# mosV2_0.net
KiCad netlist of a schematic drawn in Altium Designer
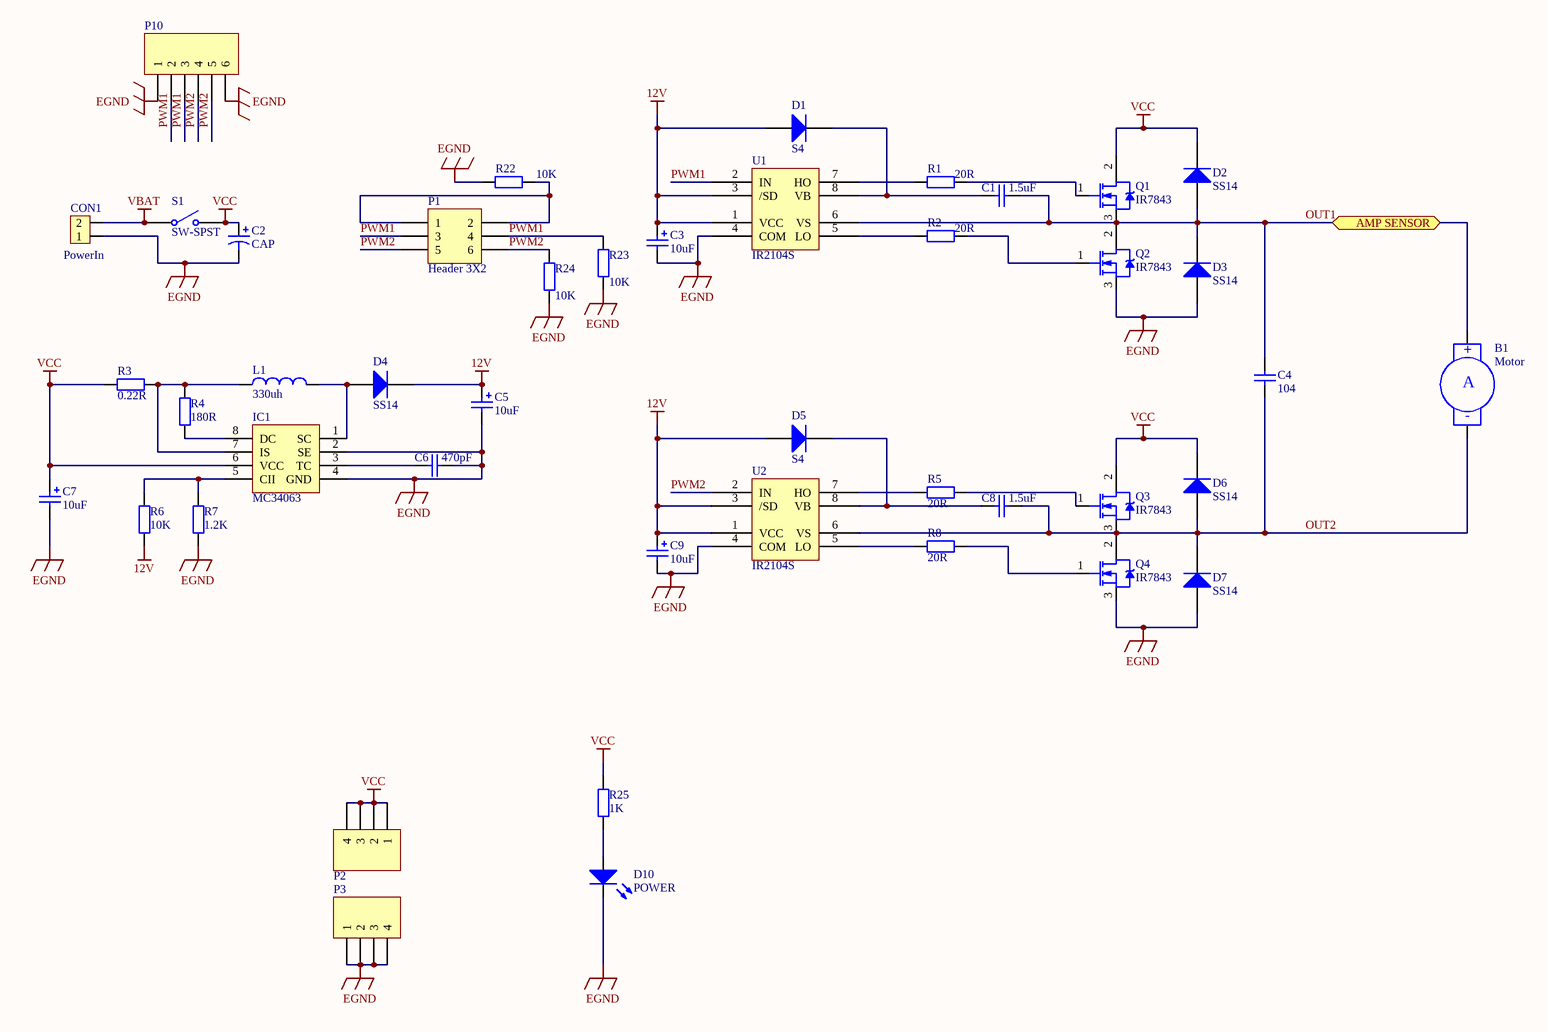
[diagram p0: 自控mosV2.0.SchDoc]

(export (version "E")
  (design (tool "Eeschema 10.0.6"))
  (components
    (comp (ref "B1")
      (value "Motor")
      (footprint "KF301-2P")
      (description "Servo Motor")
      (libsource (lib "landzo_mos") (part "Motor Servo"))
    )
    (comp (ref "C1")
      (value "1.5uF")
      (footprint "C2012")
      (description "Capacitor")
      (fields (field (name "Comment") "Cap") (field (name "PUBLISHER") "Altium Limited"))
      (libsource (lib "Miscellaneous Devices") (part "Cap"))
    )
    (comp (ref "C2") (value "CAP") (footprint "SMD-EC-F8") (libsource (lib "电赛") (part "CAP+")))
    (comp (ref "C3")
      (value "10uF")
      (footprint "C2012")
      (description "Polarized Capacitor (Radial)")
      (fields (field (name "Comment") "Cap Pol1") (field (name "PUBLISHER") "Altium Limited"))
      (libsource (lib "landzo_mos") (part "Cap Pol1"))
    )
    (comp (ref "C4")
      (value "104")
      (footprint "C2012")
      (description "Capacitor")
      (fields (field (name "Comment") "Cap") (field (name "PUBLISHER") "Altium Limited"))
      (libsource (lib "Miscellaneous Devices") (part "Cap"))
    )
    (comp (ref "C5")
      (value "10uF")
      (footprint "1206C")
      (description "Polarized Capacitor (Radial)")
      (fields (field (name "Comment") "Cap Pol1") (field (name "PUBLISHER") "Altium Limited"))
      (libsource (lib "landzo_mos") (part "Cap Pol1"))
    )
    (comp (ref "C6")
      (value "470pF")
      (footprint "C2012")
      (description "Capacitor")
      (fields (field (name "Comment") "Cap") (field (name "PUBLISHER") "Altium Limited"))
      (libsource (lib "Miscellaneous Devices") (part "Cap"))
    )
    (comp (ref "C7")
      (value "10uF")
      (footprint "1206C")
      (description "Polarized Capacitor (Radial)")
      (fields (field (name "Comment") "Cap Pol1") (field (name "PUBLISHER") "Altium Limited"))
      (libsource (lib "landzo_mos") (part "Cap Pol1"))
    )
    (comp (ref "C8")
      (value "1.5uF")
      (footprint "C2012")
      (description "Capacitor")
      (fields (field (name "Comment") "Cap") (field (name "PUBLISHER") "Altium Limited"))
      (libsource (lib "Miscellaneous Devices") (part "Cap"))
    )
    (comp (ref "C9")
      (value "10uF")
      (footprint "C2012")
      (description "Polarized Capacitor (Radial)")
      (fields (field (name "Comment") "Cap Pol1") (field (name "PUBLISHER") "Altium Limited"))
      (libsource (lib "landzo_mos") (part "Cap Pol1"))
    )
    (comp (ref "CON1")
      (value "PowerIn")
      (footprint "KF301-2P")
      (description "Header, 2-Pin")
      (libsource (lib "landzo_mos") (part "Header 2"))
    )
    (comp (ref "D1")
      (value "S4")
      (footprint "R2012")
      (description "1 Amp General Purpose Rectifier")
      (fields (field (name "PUBLISHER") "Altium Limited"))
      (libsource (lib "Miscellaneous Devices") (part "Diode 1N4007"))
    )
    (comp (ref "D2")
      (value "SS14")
      (footprint "hole-chip diode")
      (description "1 Amp General Purpose Rectifier")
      (fields (field (name "PUBLISHER") "Altium Limited"))
      (libsource (lib "Miscellaneous Devices") (part "Diode 1N4007"))
    )
    (comp (ref "D3")
      (value "SS14")
      (footprint "hole-chip diode")
      (description "1 Amp General Purpose Rectifier")
      (fields (field (name "PUBLISHER") "Altium Limited"))
      (libsource (lib "Miscellaneous Devices") (part "Diode 1N4007"))
    )
    (comp (ref "D4")
      (value "SS14")
      (footprint "hole-chip diode")
      (description "1 Amp General Purpose Rectifier")
      (fields (field (name "PUBLISHER") "Altium Limited"))
      (libsource (lib "Miscellaneous Devices") (part "Diode 1N4007"))
    )
    (comp (ref "D5")
      (value "S4")
      (footprint "R2012")
      (description "1 Amp General Purpose Rectifier")
      (fields (field (name "PUBLISHER") "Altium Limited"))
      (libsource (lib "Miscellaneous Devices") (part "Diode 1N4007"))
    )
    (comp (ref "D6")
      (value "SS14")
      (footprint "hole-chip diode")
      (description "1 Amp General Purpose Rectifier")
      (fields (field (name "PUBLISHER") "Altium Limited"))
      (libsource (lib "Miscellaneous Devices") (part "Diode 1N4007"))
    )
    (comp (ref "D7")
      (value "SS14")
      (footprint "hole-chip diode")
      (description "1 Amp General Purpose Rectifier")
      (fields (field (name "PUBLISHER") "Altium Limited"))
      (libsource (lib "Miscellaneous Devices") (part "Diode 1N4007"))
    )
    (comp (ref "D10")
      (value "POWER")
      (footprint "C2012")
      (description "Typical INFRARED GaAs LED")
      (libsource (lib "K60-V4.0") (part "LED"))
    )
    (comp (ref "IC1")
      (value "MC34063")
      (footprint "MOS motor driving module:MC34063")
      (libsource (lib "Landzo") (part "MC34063"))
    )
    (comp (ref "L1")
      (value "330uh")
      (footprint "SMD-EC-F10")
      (description "Inductor")
      (fields (field (name "PUBLISHER") "Altium Limited"))
      (libsource (lib "landzo_mos") (part "Inductor"))
    )
    (comp (ref "P1")
      (value "Header 3X2")
      (footprint "HDR2X3")
      (description "Header, 3-Pin, Dual row")
      (fields (field (name "PUBLISHER") "Altium Limited"))
      (libsource (lib "Miscellaneous Connectors") (part "Header 3X2"))
    )
    (comp (ref "P2")
      (value "Header 4")
      (footprint "HDR1X4")
      (description "Header, 4-Pin")
      (fields (field (name "PUBLISHER") "Altium Limited"))
      (libsource (lib "Sparks") (part "Header 4"))
    )
    (comp (ref "P3")
      (value "Header 4")
      (footprint "HDR1X4")
      (description "Header, 4-Pin")
      (fields (field (name "PUBLISHER") "Altium Limited"))
      (libsource (lib "") (part "Header 4_1"))
    )
    (comp (ref "P10")
      (value "Header 6")
      (footprint "FFC/SM1.0-2H6")
      (description "Header, 6-Pin")
      (fields (field (name "PUBLISHER") "Altium Limited"))
      (libsource (lib "Miscellaneous Connectors") (part "Header 6"))
    )
    (comp (ref "Q1")
      (value "IR7843")
      (footprint "LR7843")
      (description "N-Channel Power MOSFET")
      (fields (field (name "PUBLISHER") "Altium Limited"))
      (libsource (lib "MOS motor driving module ") (part "NMOS-2"))
    )
    (comp (ref "Q2")
      (value "IR7843")
      (footprint "LR7843")
      (description "N-Channel Power MOSFET")
      (fields (field (name "PUBLISHER") "Altium Limited"))
      (libsource (lib "MOS motor driving module ") (part "NMOS-2"))
    )
    (comp (ref "Q3")
      (value "IR7843")
      (footprint "LR7843")
      (description "N-Channel Power MOSFET")
      (fields (field (name "PUBLISHER") "Altium Limited"))
      (libsource (lib "MOS motor driving module ") (part "NMOS-2"))
    )
    (comp (ref "Q4")
      (value "IR7843")
      (footprint "LR7843")
      (description "N-Channel Power MOSFET")
      (fields (field (name "PUBLISHER") "Altium Limited"))
      (libsource (lib "MOS motor driving module ") (part "NMOS-2"))
    )
    (comp (ref "R1")
      (value "20R")
      (footprint "R2012")
      (description "Resistor")
      (fields (field (name "Comment") "Res2") (field (name "PUBLISHER") "Altium Limited"))
      (libsource (lib "landzo_mos") (part "Res2"))
    )
    (comp (ref "R2")
      (value "20R")
      (footprint "R2012")
      (description "Resistor")
      (fields (field (name "Comment") "Res2") (field (name "PUBLISHER") "Altium Limited"))
      (libsource (lib "landzo_mos") (part "Res2"))
    )
    (comp (ref "R3")
      (value "0.22R")
      (footprint "SK54")
      (description "Resistor")
      (fields (field (name "Comment") "Res2") (field (name "PUBLISHER") "Altium Limited"))
      (libsource (lib "landzo_mos") (part "Res2"))
    )
    (comp (ref "R4")
      (value "180R")
      (footprint "R2012")
      (description "Resistor")
      (fields (field (name "Comment") "Res2") (field (name "PUBLISHER") "Altium Limited"))
      (libsource (lib "") (part "Res2_1"))
    )
    (comp (ref "R5")
      (value "20R")
      (footprint "R2012")
      (description "Resistor")
      (fields (field (name "Comment") "Res2") (field (name "PUBLISHER") "Altium Limited"))
      (libsource (lib "landzo_mos") (part "Res2"))
    )
    (comp (ref "R6")
      (value "10K")
      (footprint "R2012")
      (description "Resistor")
      (fields (field (name "Comment") "Res2") (field (name "PUBLISHER") "Altium Limited"))
      (libsource (lib "") (part "Res2_1"))
    )
    (comp (ref "R7")
      (value "1.2K")
      (footprint "R2012")
      (description "Resistor")
      (fields (field (name "Comment") "Res2") (field (name "PUBLISHER") "Altium Limited"))
      (libsource (lib "") (part "Res2_1"))
    )
    (comp (ref "R8")
      (value "20R")
      (footprint "R2012")
      (description "Resistor")
      (fields (field (name "Comment") "Res2") (field (name "PUBLISHER") "Altium Limited"))
      (libsource (lib "landzo_mos") (part "Res2"))
    )
    (comp (ref "R22")
      (value "10K")
      (footprint "1206(2)")
      (description "Resistor")
      (fields (field (name "Comment") "Res2") (field (name "PUBLISHER") "Altium Limited"))
      (libsource (lib "Miscellaneous Devices") (part "Res2"))
    )
    (comp (ref "R23")
      (value "10K")
      (footprint "R2012")
      (description "Resistor")
      (fields (field (name "Comment") "Res2") (field (name "PUBLISHER") "Altium Limited"))
      (libsource (lib "") (part "Res2_1"))
    )
    (comp (ref "R24")
      (value "10K")
      (footprint "R2012")
      (description "Resistor")
      (fields (field (name "Comment") "Res2") (field (name "PUBLISHER") "Altium Limited"))
      (libsource (lib "") (part "Res2_1"))
    )
    (comp (ref "R25")
      (value "1K")
      (footprint "R2012")
      (description "Resistor of led")
      (libsource (lib "K60-V4.0") (part "Res"))
    )
    (comp (ref "S1")
      (value "SW-SPST")
      (footprint "SW-125V6A(-)")
      (description "Single-Pole, Single-Throw Switch")
      (fields (field (name "PUBLISHER") "Altium Limited"))
      (libsource (lib "Miscellaneous Devices") (part "SW-SPST"))
    )
    (comp (ref "U1")
      (value "IR2104S")
      (footprint "IR2104")
      (libsource (lib "MOS motor driving module ") (part "Component_1_1"))
    )
    (comp (ref "U2")
      (value "IR2104S")
      (footprint "IR2104")
      (libsource (lib "MOS motor driving module ") (part "Component_1_1"))
    )
  )
  (nets
    (net (code "1") (name "/OUT1") (class "Default")
      (node (ref "B1") (pin "1") (pinfunction "+_1") (pintype "passive"))
      (node (ref "C1") (pin "1") (pinfunction "1_1") (pintype "passive"))
      (node (ref "C4") (pin "1") (pinfunction "1_1") (pintype "passive"))
      (node (ref "D2") (pin "1") (pinfunction "A_1") (pintype "passive"))
      (node (ref "D3") (pin "2") (pinfunction "K_2") (pintype "passive"))
      (node (ref "Q1") (pin "3") (pinfunction "S_3") (pintype "passive"))
      (node (ref "Q2") (pin "2") (pinfunction "D_2") (pintype "passive"))
      (node (ref "U1") (pin "6") (pinfunction "VS_6") (pintype "passive"))
    )
    (net (code "2") (name "/OUT2") (class "Default")
      (node (ref "B1") (pin "2") (pinfunction "-_2") (pintype "passive"))
      (node (ref "C4") (pin "2") (pinfunction "2_2") (pintype "passive"))
      (node (ref "C8") (pin "1") (pinfunction "1_1") (pintype "passive"))
      (node (ref "D6") (pin "1") (pinfunction "A_1") (pintype "passive"))
      (node (ref "D7") (pin "2") (pinfunction "K_2") (pintype "passive"))
      (node (ref "Q3") (pin "3") (pinfunction "S_3") (pintype "passive"))
      (node (ref "Q4") (pin "2") (pinfunction "D_2") (pintype "passive"))
      (node (ref "U2") (pin "6") (pinfunction "VS_6") (pintype "passive"))
    )
    (net (code "3") (name "/PWM1") (class "Default")
      (node (ref "P1") (pin "3") (pinfunction "3_3") (pintype "passive"))
      (node (ref "P1") (pin "4") (pinfunction "4_4") (pintype "passive"))
      (node (ref "P10") (pin "2") (pinfunction "2_2") (pintype "passive"))
      (node (ref "P10") (pin "3") (pinfunction "3_3") (pintype "passive"))
      (node (ref "R23") (pin "2") (pinfunction "2_2") (pintype "passive"))
      (node (ref "U1") (pin "2") (pinfunction "IN_2") (pintype "passive"))
    )
    (net (code "4") (name "/PWM2") (class "Default")
      (node (ref "P1") (pin "5") (pinfunction "5_5") (pintype "passive"))
      (node (ref "P1") (pin "6") (pinfunction "6_6") (pintype "passive"))
      (node (ref "P10") (pin "4") (pinfunction "4_4") (pintype "passive"))
      (node (ref "P10") (pin "5") (pinfunction "5_5") (pintype "passive"))
      (node (ref "R24") (pin "2") (pinfunction "2_2") (pintype "passive"))
      (node (ref "U2") (pin "2") (pinfunction "IN_2") (pintype "passive"))
    )
    (net (code "5") (name "12V") (class "Default")
      (node (ref "C3") (pin "1") (pinfunction "1_1") (pintype "passive"))
      (node (ref "C5") (pin "1") (pinfunction "1_1") (pintype "passive"))
      (node (ref "C9") (pin "1") (pinfunction "1_1") (pintype "passive"))
      (node (ref "D1") (pin "1") (pinfunction "A_1") (pintype "passive"))
      (node (ref "D4") (pin "2") (pinfunction "K_2") (pintype "passive"))
      (node (ref "D5") (pin "1") (pinfunction "A_1") (pintype "passive"))
      (node (ref "R6") (pin "1") (pinfunction "1_1") (pintype "passive"))
      (node (ref "U1") (pin "1") (pinfunction "VCC_1") (pintype "passive"))
      (node (ref "U1") (pin "3") (pinfunction "/SD_3") (pintype "passive"))
      (node (ref "U2") (pin "1") (pinfunction "VCC_1") (pintype "passive"))
      (node (ref "U2") (pin "3") (pinfunction "/SD_3") (pintype "passive"))
    )
    (net (code "6") (name "EGND") (class "Default")
      (node (ref "C2") (pin "2") (pinfunction "2_2") (pintype "passive"))
      (node (ref "C3") (pin "2") (pinfunction "2_2") (pintype "passive"))
      (node (ref "C5") (pin "2") (pinfunction "2_2") (pintype "passive"))
      (node (ref "C6") (pin "1") (pinfunction "1_1") (pintype "passive"))
      (node (ref "C7") (pin "2") (pinfunction "2_2") (pintype "passive"))
      (node (ref "C9") (pin "2") (pinfunction "2_2") (pintype "passive"))
      (node (ref "CON1") (pin "1") (pinfunction "1_1") (pintype "passive"))
      (node (ref "D10") (pin "2") (pinfunction "2_2") (pintype "passive"))
      (node (ref "D3") (pin "1") (pinfunction "A_1") (pintype "passive"))
      (node (ref "D7") (pin "1") (pinfunction "A_1") (pintype "passive"))
      (node (ref "IC1") (pin "2") (pinfunction "SE_2") (pintype "passive"))
      (node (ref "IC1") (pin "4") (pinfunction "GND_4") (pintype "passive"))
      (node (ref "P10") (pin "1") (pinfunction "1_1") (pintype "passive"))
      (node (ref "P10") (pin "6") (pinfunction "6_6") (pintype "passive"))
      (node (ref "P3") (pin "1") (pinfunction "1_1") (pintype "passive"))
      (node (ref "P3") (pin "2") (pinfunction "2_2") (pintype "passive"))
      (node (ref "P3") (pin "3") (pinfunction "3_3") (pintype "passive"))
      (node (ref "P3") (pin "4") (pinfunction "4_4") (pintype "passive"))
      (node (ref "Q2") (pin "3") (pinfunction "S_3") (pintype "passive"))
      (node (ref "Q4") (pin "3") (pinfunction "S_3") (pintype "passive"))
      (node (ref "R22") (pin "1") (pinfunction "1_1") (pintype "passive"))
      (node (ref "R23") (pin "1") (pinfunction "1_1") (pintype "passive"))
      (node (ref "R24") (pin "1") (pinfunction "1_1") (pintype "passive"))
      (node (ref "R7") (pin "1") (pinfunction "1_1") (pintype "passive"))
      (node (ref "U1") (pin "4") (pinfunction "COM_4") (pintype "passive"))
      (node (ref "U2") (pin "4") (pinfunction "COM_4") (pintype "passive"))
    )
    (net (code "7") (name "Net-(D1-K)") (class "Default")
      (node (ref "C1") (pin "2") (pinfunction "2_2") (pintype "passive"))
      (node (ref "D1") (pin "2") (pinfunction "K_2") (pintype "passive"))
      (node (ref "U1") (pin "8") (pinfunction "VB_8") (pintype "passive"))
    )
    (net (code "8") (name "Net-(D4-A)") (class "Default")
      (node (ref "D4") (pin "1") (pinfunction "A_1") (pintype "passive"))
      (node (ref "IC1") (pin "1") (pinfunction "SC_1") (pintype "passive"))
      (node (ref "L1") (pin "2") (pinfunction "2_2") (pintype "passive"))
    )
    (net (code "9") (name "Net-(D5-K)") (class "Default")
      (node (ref "C8") (pin "2") (pinfunction "2_2") (pintype "passive"))
      (node (ref "D5") (pin "2") (pinfunction "K_2") (pintype "passive"))
      (node (ref "U2") (pin "8") (pinfunction "VB_8") (pintype "passive"))
    )
    (net (code "10") (name "Net-(D10-Pad1)") (class "Default")
      (node (ref "D10") (pin "1") (pinfunction "1_1") (pintype "passive"))
      (node (ref "R25") (pin "1") (pinfunction "1_1") (pintype "passive"))
    )
    (net (code "11") (name "Net-(IC1-CII)") (class "Default")
      (node (ref "IC1") (pin "5") (pinfunction "CII_5") (pintype "passive"))
      (node (ref "R6") (pin "2") (pinfunction "2_2") (pintype "passive"))
      (node (ref "R7") (pin "2") (pinfunction "2_2") (pintype "passive"))
    )
    (net (code "12") (name "Net-(IC1-DC)") (class "Default")
      (node (ref "IC1") (pin "8") (pinfunction "DC_8") (pintype "passive"))
      (node (ref "R4") (pin "1") (pinfunction "1_1") (pintype "passive"))
    )
    (net (code "13") (name "Net-(IC1-IS)") (class "Default")
      (node (ref "IC1") (pin "7") (pinfunction "IS_7") (pintype "passive"))
      (node (ref "L1") (pin "1") (pinfunction "1_1") (pintype "passive"))
      (node (ref "R3") (pin "2") (pinfunction "2_2") (pintype "passive"))
      (node (ref "R4") (pin "2") (pinfunction "2_2") (pintype "passive"))
    )
    (net (code "14") (name "Net-(IC1-TC)") (class "Default")
      (node (ref "C6") (pin "2") (pinfunction "2_2") (pintype "passive"))
      (node (ref "IC1") (pin "3") (pinfunction "TC_3") (pintype "passive"))
    )
    (net (code "15") (name "Net-(P1-Pad1)") (class "Default")
      (node (ref "P1") (pin "1") (pinfunction "1_1") (pintype "passive"))
      (node (ref "P1") (pin "2") (pinfunction "2_2") (pintype "passive"))
      (node (ref "R22") (pin "2") (pinfunction "2_2") (pintype "passive"))
    )
    (net (code "16") (name "Net-(Q1-G)") (class "Default")
      (node (ref "Q1") (pin "1") (pinfunction "G_1") (pintype "passive"))
      (node (ref "R1") (pin "2") (pinfunction "2_2") (pintype "passive"))
    )
    (net (code "17") (name "Net-(Q2-G)") (class "Default")
      (node (ref "Q2") (pin "1") (pinfunction "G_1") (pintype "passive"))
      (node (ref "R2") (pin "2") (pinfunction "2_2") (pintype "passive"))
    )
    (net (code "18") (name "Net-(Q3-G)") (class "Default")
      (node (ref "Q3") (pin "1") (pinfunction "G_1") (pintype "passive"))
      (node (ref "R5") (pin "2") (pinfunction "2_2") (pintype "passive"))
    )
    (net (code "19") (name "Net-(Q4-G)") (class "Default")
      (node (ref "Q4") (pin "1") (pinfunction "G_1") (pintype "passive"))
      (node (ref "R8") (pin "2") (pinfunction "2_2") (pintype "passive"))
    )
    (net (code "20") (name "Net-(U1-HO)") (class "Default")
      (node (ref "R1") (pin "1") (pinfunction "1_1") (pintype "passive"))
      (node (ref "U1") (pin "7") (pinfunction "HO_7") (pintype "passive"))
    )
    (net (code "21") (name "Net-(U1-LO)") (class "Default")
      (node (ref "R2") (pin "1") (pinfunction "1_1") (pintype "passive"))
      (node (ref "U1") (pin "5") (pinfunction "LO_5") (pintype "passive"))
    )
    (net (code "22") (name "Net-(U2-HO)") (class "Default")
      (node (ref "R5") (pin "1") (pinfunction "1_1") (pintype "passive"))
      (node (ref "U2") (pin "7") (pinfunction "HO_7") (pintype "passive"))
    )
    (net (code "23") (name "Net-(U2-LO)") (class "Default")
      (node (ref "R8") (pin "1") (pinfunction "1_1") (pintype "passive"))
      (node (ref "U2") (pin "5") (pinfunction "LO_5") (pintype "passive"))
    )
    (net (code "24") (name "VBAT") (class "Default")
      (node (ref "CON1") (pin "2") (pinfunction "2_2") (pintype "passive"))
      (node (ref "S1") (pin "1") (pinfunction "COMMON_1") (pintype "passive"))
    )
    (net (code "25") (name "VCC") (class "Default")
      (node (ref "C2") (pin "1") (pinfunction "1_1") (pintype "passive"))
      (node (ref "C7") (pin "1") (pinfunction "1_1") (pintype "passive"))
      (node (ref "D2") (pin "2") (pinfunction "K_2") (pintype "passive"))
      (node (ref "D6") (pin "2") (pinfunction "K_2") (pintype "passive"))
      (node (ref "IC1") (pin "6") (pinfunction "VCC_6") (pintype "passive"))
      (node (ref "P2") (pin "1") (pinfunction "1_1") (pintype "passive"))
      (node (ref "P2") (pin "2") (pinfunction "2_2") (pintype "passive"))
      (node (ref "P2") (pin "3") (pinfunction "3_3") (pintype "passive"))
      (node (ref "P2") (pin "4") (pinfunction "4_4") (pintype "passive"))
      (node (ref "Q1") (pin "2") (pinfunction "D_2") (pintype "passive"))
      (node (ref "Q3") (pin "2") (pinfunction "D_2") (pintype "passive"))
      (node (ref "R25") (pin "2") (pinfunction "2_2") (pintype "passive"))
      (node (ref "R3") (pin "1") (pinfunction "1_1") (pintype "passive"))
      (node (ref "S1") (pin "2") (pinfunction "NO_2") (pintype "passive"))
    )
  )
)
